# oscillator-20MHz.net
KiCad netlist of a schematic drawn in Altium Designer
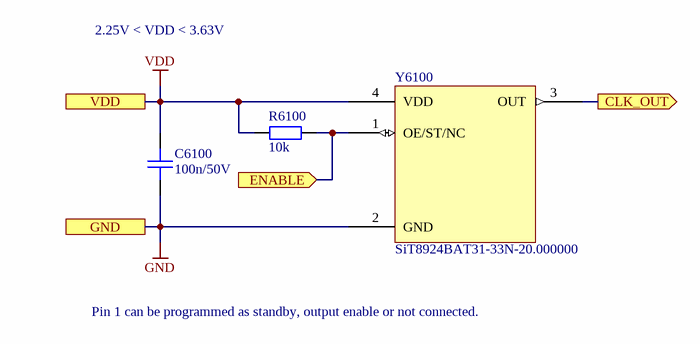
[diagram p0: oscillator-20MHz.SchDoc]

(export (version "E")
  (design (tool "Eeschema 10.0.6"))
  (components
    (comp (ref "C6100")
      (value "100n/50V")
      (footprint "CAPC1005X06N")
      (description "MLCC")
      (fields (field (name "PART NUMBER") "gen_C_ceramic_100n_50V_X7R_0402"))
      (libsource (lib "OE750") (part "C"))
    )
    (comp (ref "R6100")
      (value "10k")
      (footprint "RESC1005X04N")
      (description "SMD Resistor 10k 0402")
      (fields (field (name "PART NUMBER") "gen_R_10k_0402") (field (name "TOLERANCE") "1%"))
      (libsource (lib "OE750") (part "R"))
    )
    (comp (ref "Y6100")
      (value "SiT8924BAT31-33N-20.000000")
      (footprint "SiT8924xx-3x")
      (description "Automotive AEC-Q100 Oscillator 20MHz")
      (fields (field (name "MANUFACTURER") "SiTime"))
      (libsource (lib "OE750") (part "SiT8924"))
    )
  )
  (nets
    (net (code "1") (name "/CLK_OUT") (class "Default")
      (node (ref "Y6100") (pin "3") (pinfunction "OUT_3") (pintype "output"))
    )
    (net (code "2") (name "/ENABLE") (class "Default")
      (node (ref "R6100") (pin "2") (pinfunction "2_2") (pintype "passive"))
      (node (ref "Y6100") (pin "1") (pinfunction "OE/ST/NC_1") (pintype "bidirectional"))
    )
    (net (code "3") (name "GND") (class "Default")
      (node (ref "C6100") (pin "1") (pinfunction "1_1") (pintype "passive"))
      (node (ref "Y6100") (pin "2") (pinfunction "GND_2") (pintype "power_in"))
    )
    (net (code "4") (name "VDD") (class "Default")
      (node (ref "C6100") (pin "2") (pinfunction "2_2") (pintype "passive"))
      (node (ref "R6100") (pin "1") (pinfunction "1_1") (pintype "passive"))
      (node (ref "Y6100") (pin "4") (pinfunction "VDD_4") (pintype "power_in"))
    )
  )
)
